# Low_Pass_48kHz.net
KiCad netlist of a schematic drawn in Altium Designer
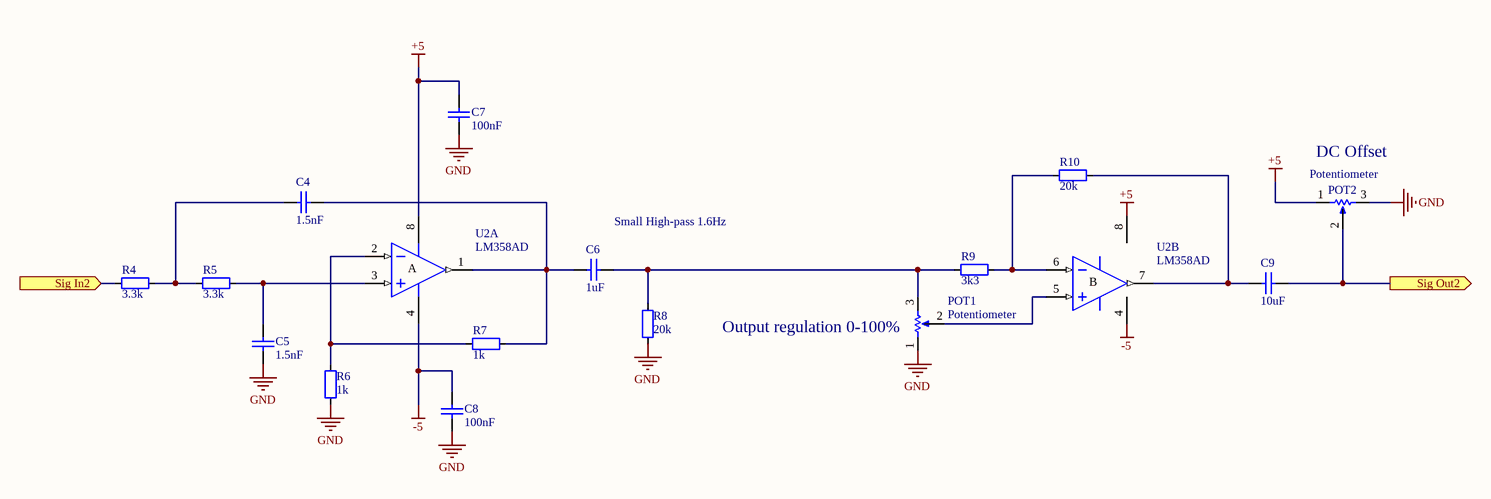
[diagram p0: Low_Pass_48kHz.SchDoc]

(export (version "E")
  (design (tool "Eeschema 10.0.6"))
  (components
    (comp (ref "C4")
      (value "1.5nF")
      (footprint "CAPC0603M")
      (description "Ceramic capacitor")
      (fields (field (name "Comment") "Cap"))
      (libsource (lib "KNR_Kurs") (part "Cap"))
    )
    (comp (ref "C5")
      (value "1.5nF")
      (footprint "CAPC0603M")
      (description "Ceramic capacitor")
      (fields (field (name "Comment") "Cap"))
      (libsource (lib "KNR_Kurs") (part "Cap"))
    )
    (comp (ref "C6")
      (value "1uF")
      (footprint "CAPC0603M")
      (description "Ceramic capacitor")
      (fields (field (name "Comment") "Cap"))
      (libsource (lib "KNR_Kurs") (part "Cap"))
    )
    (comp (ref "C7")
      (value "100nF")
      (footprint "CAPC0603M")
      (description "Ceramic capacitor")
      (fields (field (name "Comment") "Cap"))
      (libsource (lib "KNR_Kurs") (part "Cap"))
    )
    (comp (ref "C8")
      (value "100nF")
      (footprint "CAPC0603M")
      (description "Ceramic capacitor")
      (fields (field (name "Comment") "Cap"))
      (libsource (lib "KNR_Kurs") (part "Cap"))
    )
    (comp (ref "C9")
      (value "10uF")
      (footprint "CAPC0603M")
      (description "Ceramic capacitor")
      (fields (field (name "Comment") "Cap"))
      (libsource (lib "KNR_Kurs") (part "Cap"))
    )
    (comp (ref "POT1")
      (value "Potentiometer")
      (footprint "Pot_3296")
      (libsource (lib "KNR_Kurs") (part "Potentiometer"))
    )
    (comp (ref "POT2")
      (value "Potentiometer")
      (footprint "Pot_3296")
      (libsource (lib "KNR_Kurs") (part "Potentiometer"))
    )
    (comp (ref "R4")
      (value "3.3k")
      (footprint "RESC0603")
      (description "Resistior")
      (libsource (lib "KNR_Kurs") (part "RES"))
    )
    (comp (ref "R5")
      (value "3.3k")
      (footprint "RESC0603")
      (description "Resistior")
      (libsource (lib "KNR_Kurs") (part "RES"))
    )
    (comp (ref "R6")
      (value "1k")
      (footprint "RESC0603")
      (description "Resistior")
      (libsource (lib "") (part "RES_1"))
    )
    (comp (ref "R7")
      (value "1k")
      (footprint "RESC0603")
      (description "Resistior")
      (libsource (lib "KNR_Kurs") (part "RES"))
    )
    (comp (ref "R8")
      (value "20k")
      (footprint "RESC0603")
      (description "Resistior")
      (libsource (lib "") (part "RES_1"))
    )
    (comp (ref "R9")
      (value "3k3")
      (footprint "RESC0603")
      (description "Resistior")
      (libsource (lib "") (part "RES_2"))
    )
    (comp (ref "R10")
      (value "20k")
      (footprint "RESC0603")
      (description "Resistior")
      (libsource (lib "") (part "RES_2"))
    )
    (comp (ref "U2")
      (value "LM358AD")
      (footprint "SO-8_N")
      (description "Low-Power Dual Operational Amplifier")
      (fields (field (name "PUBLISHER") "Altium Limited"))
      (libsource (lib "Library_Altium_KNR") (part "LM358AD"))
    )
  )
  (nets
    (net (code "1") (name "+5") (class "Default")
      (node (ref "C7") (pin "1") (pinfunction "1_1") (pintype "passive"))
      (node (ref "POT2") (pin "1") (pinfunction "1_1") (pintype "passive"))
      (node (ref "U2") (pin "8") (pinfunction "V+_8") (pintype "power_in"))
    )
    (net (code "2") (name "-5") (class "Default")
      (node (ref "C8") (pin "1") (pinfunction "1_1") (pintype "passive"))
      (node (ref "U2") (pin "4") (pinfunction "V-_4") (pintype "power_in"))
    )
    (net (code "3") (name "/Sig In2") (class "Default")
      (node (ref "R4") (pin "1") (pinfunction "1_1") (pintype "passive"))
    )
    (net (code "4") (name "/Sig Out2") (class "Default")
      (node (ref "C9") (pin "1") (pinfunction "1_1") (pintype "passive"))
      (node (ref "POT2") (pin "2") (pinfunction "2_2") (pintype "passive"))
    )
    (net (code "5") (name "GND") (class "Default")
      (node (ref "C5") (pin "1") (pinfunction "1_1") (pintype "passive"))
      (node (ref "C7") (pin "2") (pinfunction "2_2") (pintype "passive"))
      (node (ref "C8") (pin "2") (pinfunction "2_2") (pintype "passive"))
      (node (ref "POT1") (pin "1") (pinfunction "1_1") (pintype "passive"))
      (node (ref "POT2") (pin "3") (pinfunction "3_3") (pintype "passive"))
      (node (ref "R6") (pin "1") (pinfunction "1_1") (pintype "passive"))
      (node (ref "R8") (pin "1") (pinfunction "1_1") (pintype "passive"))
    )
    (net (code "6") (name "Net-(C4-Pad2)") (class "Default")
      (node (ref "C4") (pin "2") (pinfunction "2_2") (pintype "passive"))
      (node (ref "R4") (pin "2") (pinfunction "2_2") (pintype "passive"))
      (node (ref "R5") (pin "1") (pinfunction "1_1") (pintype "passive"))
    )
    (net (code "7") (name "Net-(C6-Pad1)") (class "Default")
      (node (ref "C6") (pin "1") (pinfunction "1_1") (pintype "passive"))
      (node (ref "POT1") (pin "3") (pinfunction "3_3") (pintype "passive"))
      (node (ref "R8") (pin "2") (pinfunction "2_2") (pintype "passive"))
      (node (ref "R9") (pin "2") (pinfunction "2_2") (pintype "passive"))
    )
    (net (code "8") (name "Net-(U2A-IN+)") (class "Default")
      (node (ref "C5") (pin "2") (pinfunction "2_2") (pintype "passive"))
      (node (ref "R5") (pin "2") (pinfunction "2_2") (pintype "passive"))
      (node (ref "U2") (pin "3") (pinfunction "IN+_3") (pintype "input"))
    )
    (net (code "9") (name "Net-(U2A-IN-)") (class "Default")
      (node (ref "R6") (pin "2") (pinfunction "2_2") (pintype "passive"))
      (node (ref "R7") (pin "1") (pinfunction "1_1") (pintype "passive"))
      (node (ref "U2") (pin "2") (pinfunction "IN-_2") (pintype "input"))
    )
    (net (code "10") (name "Net-(U2A-OUT)") (class "Default")
      (node (ref "C4") (pin "1") (pinfunction "1_1") (pintype "passive"))
      (node (ref "C6") (pin "2") (pinfunction "2_2") (pintype "passive"))
      (node (ref "R7") (pin "2") (pinfunction "2_2") (pintype "passive"))
      (node (ref "U2") (pin "1") (pinfunction "OUT_1") (pintype "output"))
    )
    (net (code "11") (name "Net-(U2B-IN+)") (class "Default")
      (node (ref "POT1") (pin "2") (pinfunction "2_2") (pintype "passive"))
      (node (ref "U2") (pin "5") (pinfunction "IN+_5") (pintype "input"))
    )
    (net (code "12") (name "Net-(U2B-IN-)") (class "Default")
      (node (ref "R10") (pin "2") (pinfunction "2_2") (pintype "passive"))
      (node (ref "R9") (pin "1") (pinfunction "1_1") (pintype "passive"))
      (node (ref "U2") (pin "6") (pinfunction "IN-_6") (pintype "input"))
    )
    (net (code "13") (name "Net-(U2B-OUT)") (class "Default")
      (node (ref "C9") (pin "2") (pinfunction "2_2") (pintype "passive"))
      (node (ref "R10") (pin "1") (pinfunction "1_1") (pintype "passive"))
      (node (ref "U2") (pin "7") (pinfunction "OUT_7") (pintype "output"))
    )
  )
)
